# P03_SOM_CONNECTOR.net
KiCad netlist of a schematic drawn in Altium Designer
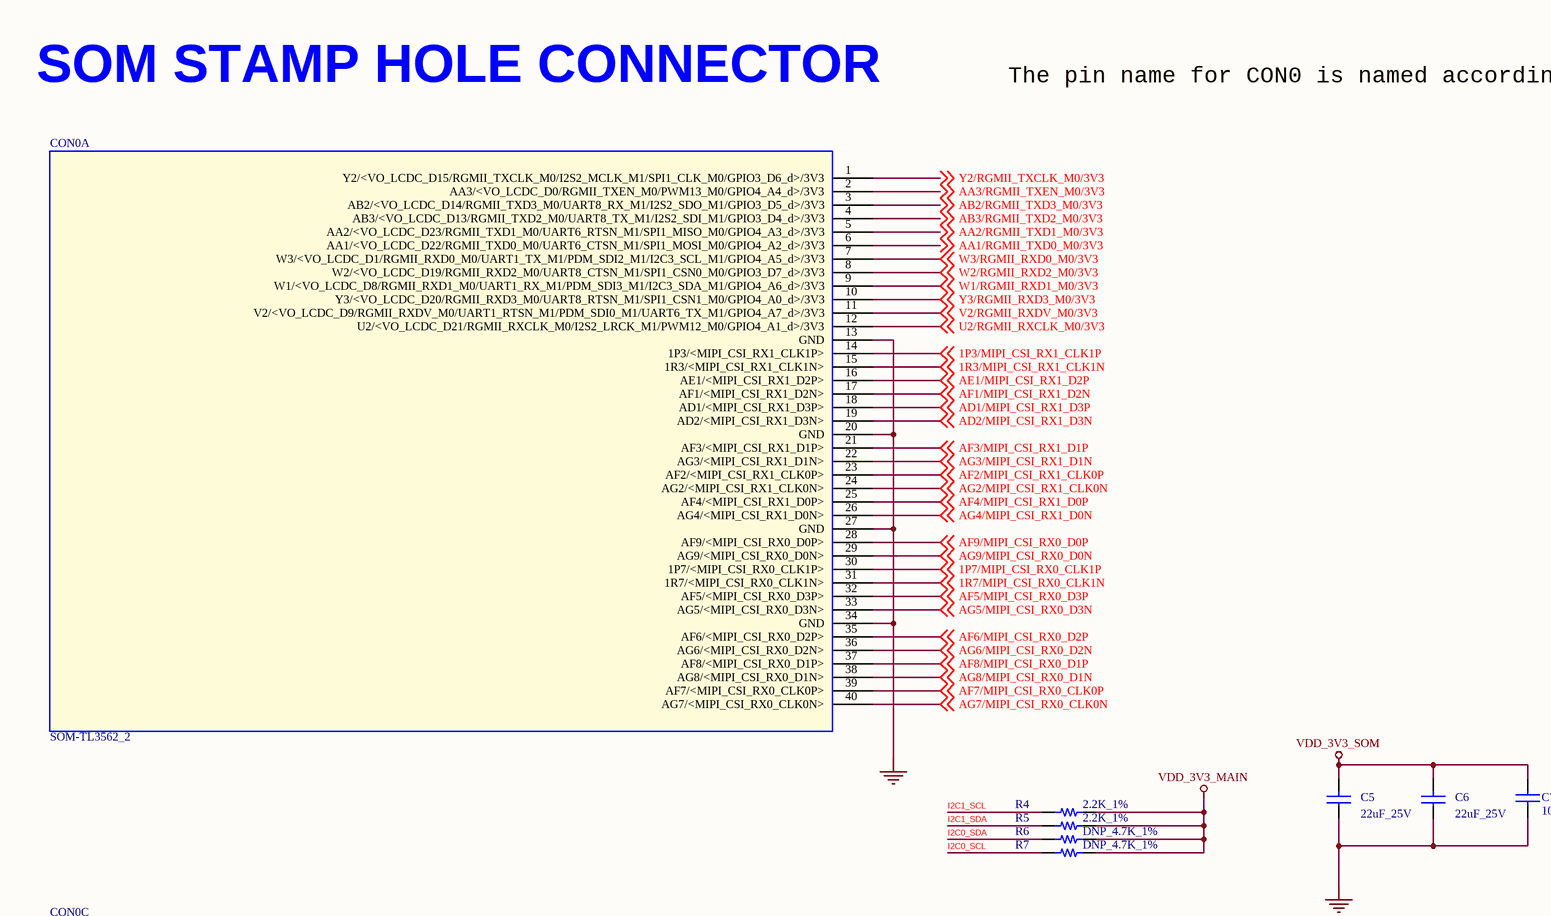
[diagram p0: P03_SOM CONNECTOR.SchDoc, top left]
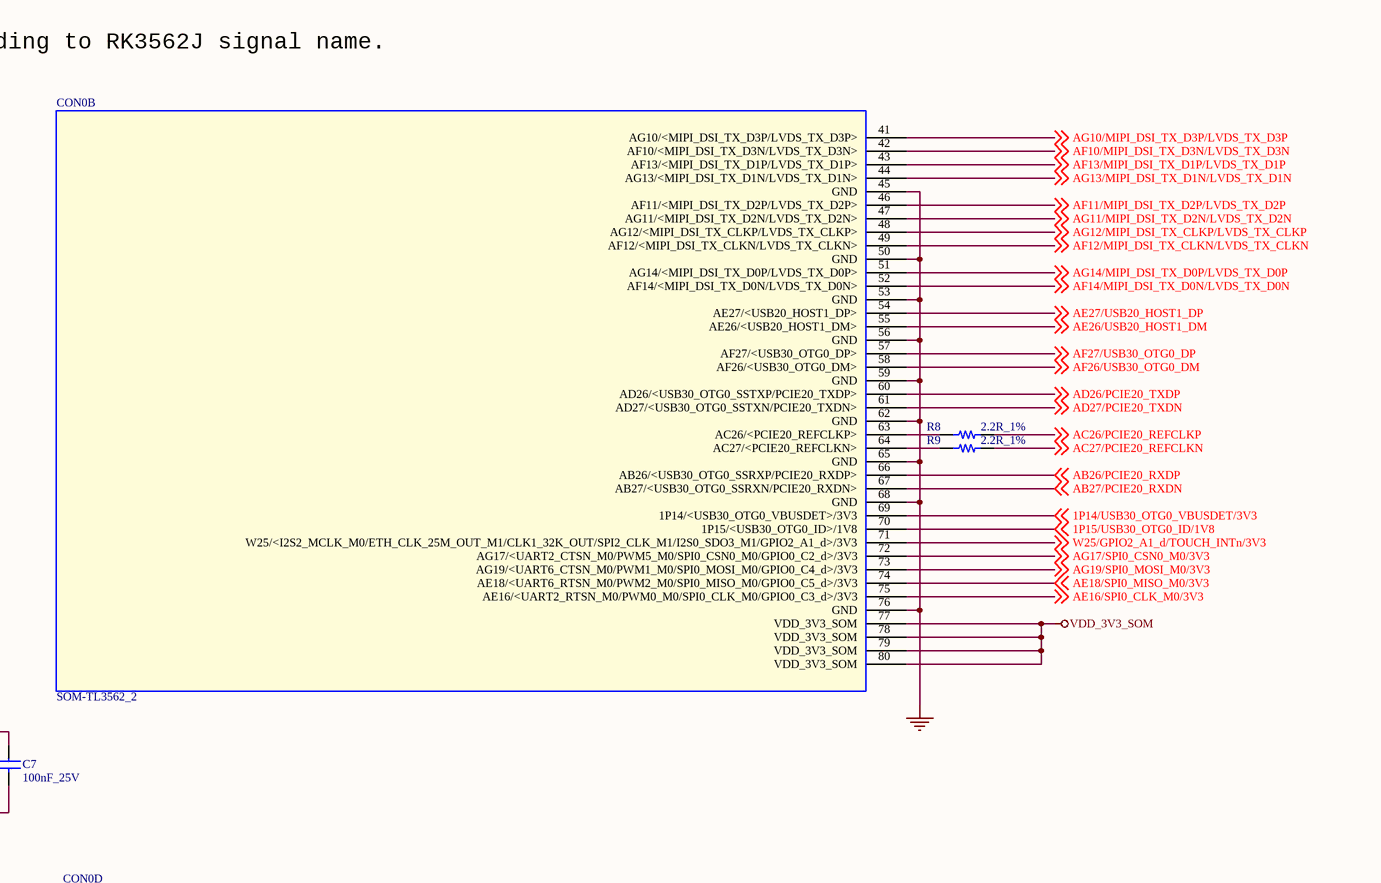
[diagram p1: P03_SOM CONNECTOR.SchDoc, top right]
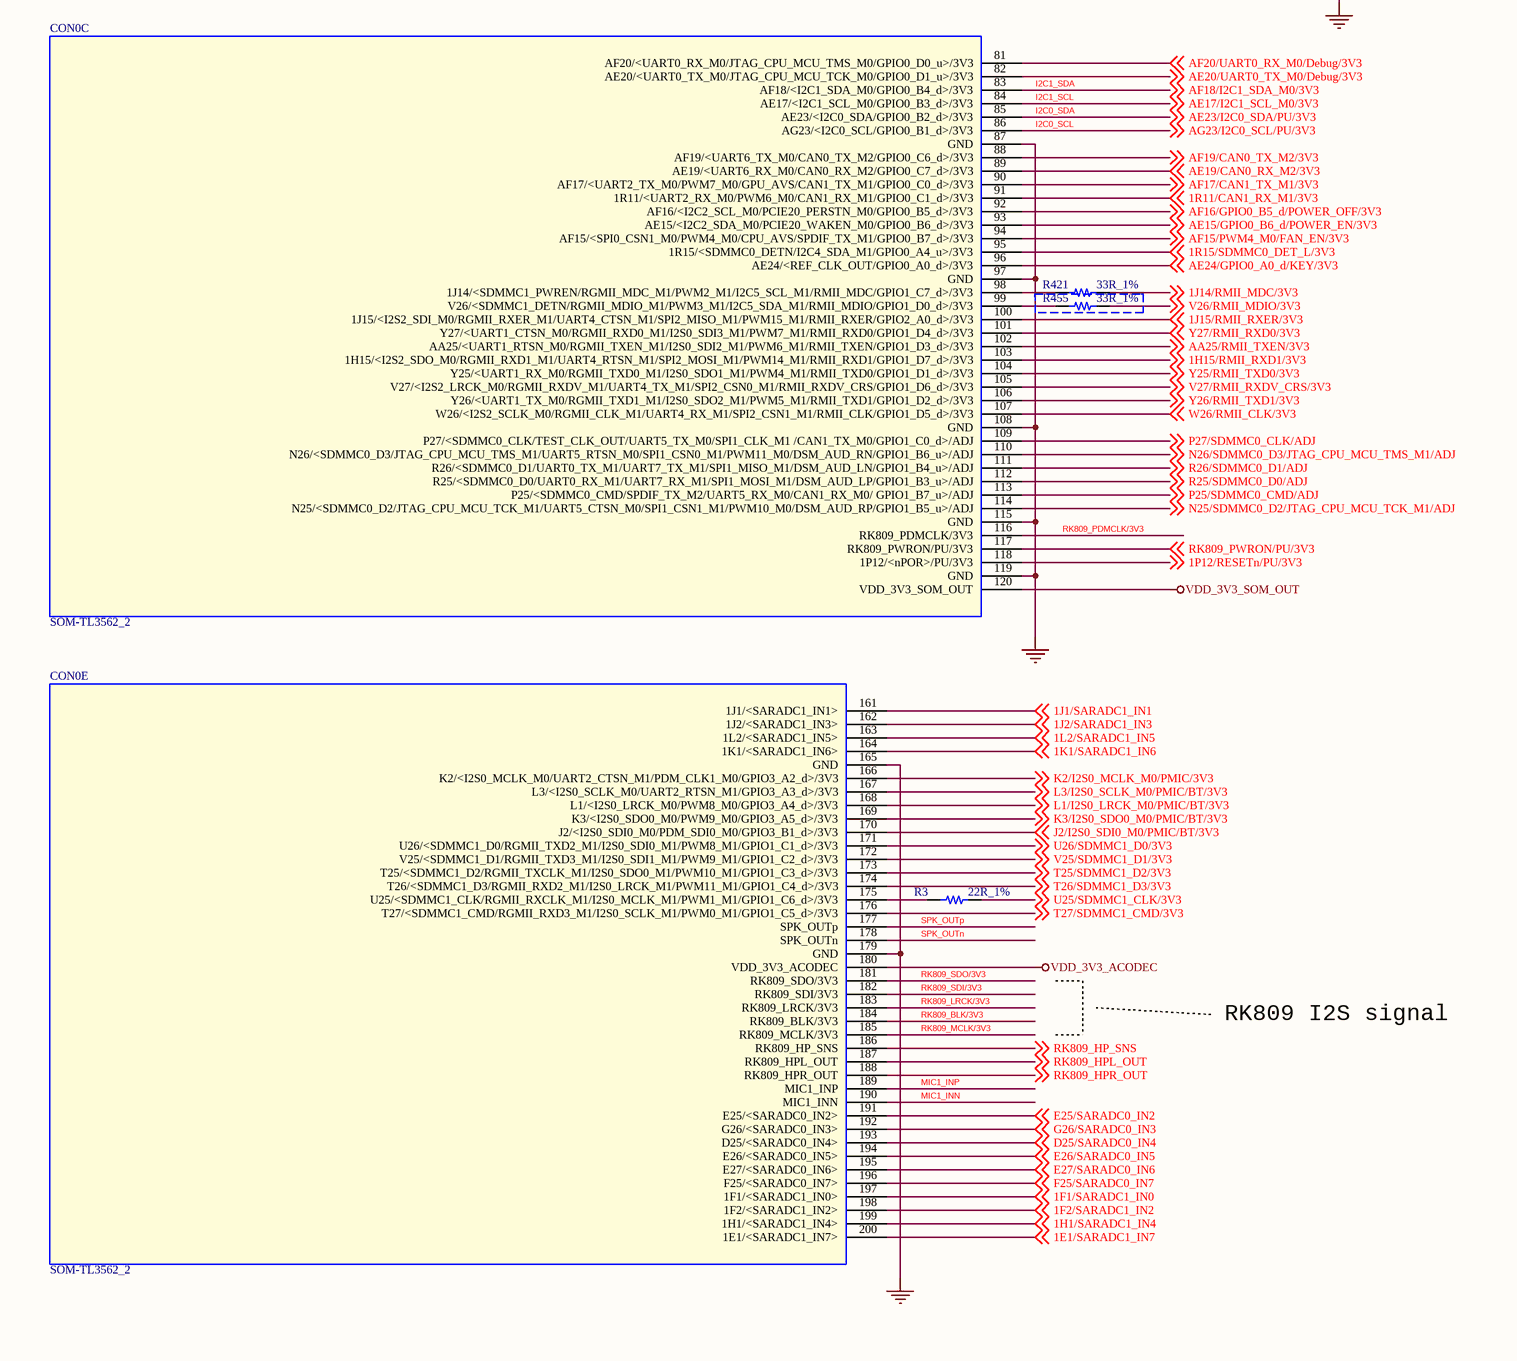
[diagram p2: P03_SOM CONNECTOR.SchDoc, bottom left]
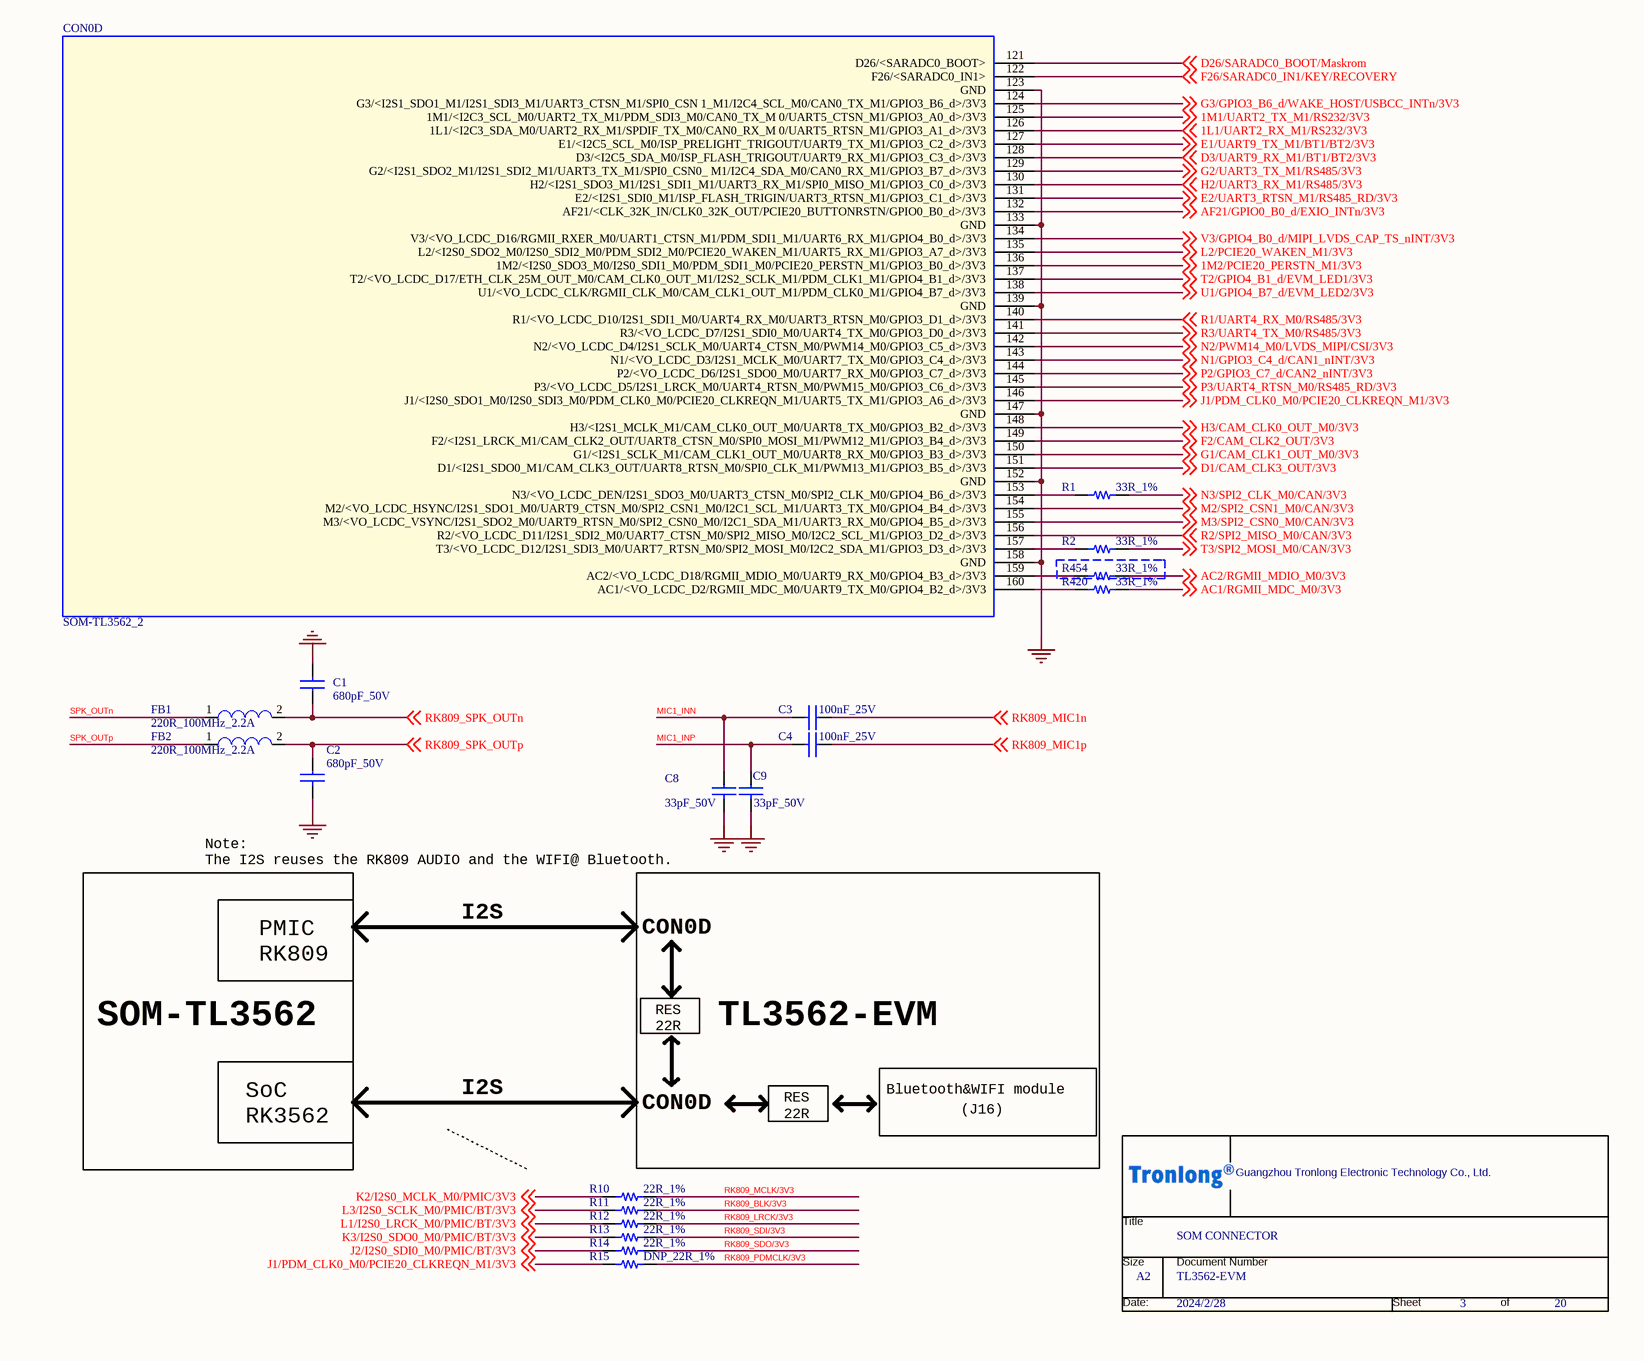
[diagram p3: P03_SOM CONNECTOR.SchDoc, bottom right]

(export (version "E")
  (design (tool "Eeschema 10.0.6"))
  (components
    (comp (ref "C1")
      (value "680pF_50V")
      (footprint "C0603")
      (description "贴片陶瓷电容,680pF,5%,50V,COG")
      (fields
        (field (name "TOLERANCE") "5%")
        (field (name "VOLTAGE") "50V")
        (field (name "CREATED BY") "JJJ")
      )
      (libsource (lib "*") (part "CAP NP_Dup3"))
    )
    (comp (ref "C2")
      (value "680pF_50V")
      (footprint "C0603")
      (description "贴片陶瓷电容,680pF,5%,50V,COG")
      (fields
        (field (name "VOLTAGE") "50V")
        (field (name "TOLERANCE") "5%")
        (field (name "CREATED BY") "JJJ")
      )
      (libsource (lib "*") (part "CAP NP_Dup3"))
    )
    (comp (ref "C3")
      (value "100nF_25V")
      (footprint "C0402")
      (description "贴片陶瓷电容,100nF,10%,25V,X5R")
      (fields
        (field (name "VOLTAGE") "10V")
        (field (name "TOLERANCE") "10%")
        (field (name "CREATED BY") "JJJ")
      )
      (libsource (lib "*") (part "CAP NP_Dup3"))
    )
    (comp (ref "C4")
      (value "100nF_25V")
      (footprint "C0402")
      (description "贴片陶瓷电容,100nF,10%,25V,X5R")
      (fields
        (field (name "TOLERANCE") "10%")
        (field (name "VOLTAGE") "10V")
        (field (name "CREATED BY") "JJJ")
      )
      (libsource (lib "*") (part "CAP NP_Dup3"))
    )
    (comp (ref "C5")
      (value "22uF_25V")
      (footprint "C0805")
      (description "贴片陶瓷电容,22uF,20%,25V,X5R")
      (fields
        (field (name "TOLERANCE") "10%")
        (field (name "VOLTAGE") "10V")
        (field (name "CREATED BY") "JJJ")
      )
      (libsource (lib "*") (part "CAP NP"))
    )
    (comp (ref "C6")
      (value "22uF_25V")
      (footprint "C0805")
      (description "贴片陶瓷电容,22uF,20%,25V,X5R")
      (fields
        (field (name "TOLERANCE") "10%")
        (field (name "VOLTAGE") "10V")
        (field (name "CREATED BY") "JJJ")
      )
      (libsource (lib "*") (part "CAP NP"))
    )
    (comp (ref "C7")
      (value "100nF_25V")
      (footprint "C0402")
      (description "贴片陶瓷电容,100nF,10%,25V,X5R")
      (fields
        (field (name "VOLTAGE") "10V")
        (field (name "TOLERANCE") "10%")
        (field (name "CREATED BY") "JJJ")
      )
      (libsource (lib "*") (part "CAP NP"))
    )
    (comp (ref "C8")
      (value "33pF_50V")
      (footprint "C0603")
      (description "贴片陶瓷电容,33pF,5%,50V,COG")
      (fields
        (field (name "VOLTAGE") "50V")
        (field (name "TOLERANCE") "5%")
        (field (name "CREATED BY") "JJJ")
      )
      (libsource (lib "*") (part "CAP NP_Dup3"))
    )
    (comp (ref "C9")
      (value "33pF_50V")
      (footprint "C0603")
      (description "贴片陶瓷电容,33pF,5%,50V,COG")
      (fields
        (field (name "VOLTAGE") "50V")
        (field (name "TOLERANCE") "5%")
        (field (name "CREATED BY") "JJJ")
      )
      (libsource (lib "*") (part "CAP NP_Dup3"))
    )
    (comp (ref "CON0")
      (value "SOM-TL3562_2")
      (footprint "TL3562-MiniEVM-new:SMD_200P_45x45_TL3562")
      (fields
        (field (name "MANUFACTURER") "广州创龙电子科技有限公司（Tronlong）")
        (field (name "MANUFACTURER PARTNUMBER") "SMD_200P_45x45_TL3562")
      )
      (libsource (lib "*") (part "SOM-TL3562_2"))
    )
    (comp (ref "FB1")
      (value "220R_100MHz_2.2A")
      (footprint "L0603")
      (description "磁珠,50mΩ,2.2A,220R@100MHz")
      (fields
        (field (name "MANUFACTURER PARTNUMBER") "UPZ1608U221-2R2TF")
        (field (name "MANUFACTURER") "深圳顺络电子股份有限公司（Sunlord）")
        (field (name "CREATED BY") "YTL")
      )
      (libsource (lib "*") (part "BEAD"))
    )
    (comp (ref "FB2")
      (value "220R_100MHz_2.2A")
      (footprint "L0603")
      (description "磁珠,50mΩ,2.2A,220R@100MHz")
      (fields
        (field (name "MANUFACTURER") "深圳顺络电子股份有限公司（Sunlord）")
        (field (name "MANUFACTURER PARTNUMBER") "UPZ1608U221-2R2TF")
        (field (name "CREATED BY") "YTL")
      )
      (libsource (lib "*") (part "BEAD"))
    )
    (comp (ref "R1")
      (value "33R_1%")
      (footprint "R0402")
      (description "贴片电阻,33R,±1%,1/16W")
      (libsource (lib "*") (part "Resistor_Dup3"))
    )
    (comp (ref "R2")
      (value "33R_1%")
      (footprint "R0402")
      (description "贴片电阻,33R,±1%,1/16W")
      (libsource (lib "*") (part "Resistor_Dup3"))
    )
    (comp (ref "R3")
      (value "22R_1%")
      (footprint "R0402")
      (description "贴片电阻,22R,±1%,1/16W")
      (libsource (lib "*") (part "Resistor_Dup3"))
    )
    (comp (ref "R4")
      (value "2.2K_1%")
      (footprint "R0603")
      (description "贴片电阻,2.2K,±1%,1/10W")
      (libsource (lib "*") (part "Resistor_Dup3"))
    )
    (comp (ref "R5")
      (value "2.2K_1%")
      (footprint "R0603")
      (description "贴片电阻,2.2K,±1%,1/10W")
      (libsource (lib "*") (part "Resistor_Dup3"))
    )
    (comp (ref "R6")
      (value "DNP_4.7K_1%")
      (footprint "R0402")
      (description "贴片电阻,4.7K,±1%,1/16W")
      (libsource (lib "*") (part "Resistor_Dup3"))
    )
    (comp (ref "R7")
      (value "DNP_4.7K_1%")
      (footprint "R0402")
      (description "贴片电阻,4.7K,±1%,1/16W")
      (libsource (lib "*") (part "Resistor_Dup3"))
    )
    (comp (ref "R8")
      (value "2.2R_1%")
      (footprint "R0402")
      (description "贴片电阻,2.2R,±1%,1/16W")
      (libsource (lib "*") (part "Resistor_Dup3"))
    )
    (comp (ref "R9")
      (value "2.2R_1%")
      (footprint "R0402")
      (description "贴片电阻,2.2R,±1%,1/16W")
      (libsource (lib "*") (part "Resistor_Dup3"))
    )
    (comp (ref "R10")
      (value "22R_1%")
      (footprint "R0402")
      (description "贴片电阻,22R,±1%,1/16W")
      (libsource (lib "*") (part "Resistor_Dup3"))
    )
    (comp (ref "R11")
      (value "22R_1%")
      (footprint "R0402")
      (description "贴片电阻,22R,±1%,1/16W")
      (libsource (lib "*") (part "Resistor_Dup3"))
    )
    (comp (ref "R12")
      (value "22R_1%")
      (footprint "R0402")
      (description "贴片电阻,22R,±1%,1/16W")
      (libsource (lib "*") (part "Resistor_Dup3"))
    )
    (comp (ref "R13")
      (value "22R_1%")
      (footprint "R0402")
      (description "贴片电阻,22R,±1%,1/16W")
      (libsource (lib "*") (part "Resistor_Dup3"))
    )
    (comp (ref "R14")
      (value "22R_1%")
      (footprint "R0402")
      (description "贴片电阻,22R,±1%,1/16W")
      (libsource (lib "*") (part "Resistor_Dup3"))
    )
    (comp (ref "R15")
      (value "DNP_22R_1%")
      (footprint "R0402")
      (description "贴片电阻,22R,±1%,1/16W")
      (libsource (lib "*") (part "Resistor_Dup3"))
    )
    (comp (ref "R420")
      (value "33R_1%")
      (footprint "R0402")
      (description "贴片电阻,33R,±1%,1/16W")
      (libsource (lib "*") (part "Resistor_Dup3"))
    )
    (comp (ref "R421")
      (value "33R_1%")
      (footprint "R0402")
      (description "贴片电阻,33R,±1%,1/16W")
      (libsource (lib "*") (part "Resistor_Dup3"))
    )
    (comp (ref "R454")
      (value "33R_1%")
      (footprint "R0402")
      (description "贴片电阻,33R,±1%,1/16W")
      (libsource (lib "*") (part "Resistor_Dup3"))
    )
    (comp (ref "R455")
      (value "33R_1%")
      (footprint "R0402")
      (description "贴片电阻,33R,±1%,1/16W")
      (libsource (lib "*") (part "Resistor_Dup3"))
    )
  )
  (nets
    (net (code "1") (name "/MIC1_INN") (class "Default")
      (node (ref "C3") (pin "2") (pinfunction "2_2") (pintype "passive"))
      (node (ref "C8") (pin "1") (pinfunction "1_1") (pintype "passive"))
      (node (ref "CON0") (pin "190") (pinfunction "MIC1_INN_190") (pintype "passive"))
    )
    (net (code "2") (name "/MIC1_INP") (class "Default")
      (node (ref "C4") (pin "2") (pinfunction "2_2") (pintype "passive"))
      (node (ref "C9") (pin "1") (pinfunction "1_1") (pintype "passive"))
      (node (ref "CON0") (pin "189") (pinfunction "MIC1_INP_189") (pintype "passive"))
    )
    (net (code "3") (name "/RK809_BLK{slash}3V3") (class "Default")
      (node (ref "CON0") (pin "184") (pinfunction "RK809_BLK/3V3_184") (pintype "passive"))
      (node (ref "R11") (pin "2") (pinfunction "2_2") (pintype "passive"))
    )
    (net (code "4") (name "/RK809_LRCK{slash}3V3") (class "Default")
      (node (ref "CON0") (pin "183") (pinfunction "RK809_LRCK/3V3_183") (pintype "passive"))
      (node (ref "R12") (pin "2") (pinfunction "2_2") (pintype "passive"))
    )
    (net (code "5") (name "/RK809_MCLK{slash}3V3") (class "Default")
      (node (ref "CON0") (pin "185") (pinfunction "RK809_MCLK/3V3_185") (pintype "passive"))
      (node (ref "R10") (pin "2") (pinfunction "2_2") (pintype "passive"))
    )
    (net (code "6") (name "/RK809_PDMCLK{slash}3V3") (class "Default")
      (node (ref "CON0") (pin "116") (pinfunction "RK809_PDMCLK/3V3_116") (pintype "passive"))
      (node (ref "R15") (pin "2") (pinfunction "2_2") (pintype "passive"))
    )
    (net (code "7") (name "/RK809_SDI{slash}3V3") (class "Default")
      (node (ref "CON0") (pin "182") (pinfunction "RK809_SDI/3V3_182") (pintype "passive"))
      (node (ref "R13") (pin "2") (pinfunction "2_2") (pintype "passive"))
    )
    (net (code "8") (name "/RK809_SDO{slash}3V3") (class "Default")
      (node (ref "CON0") (pin "181") (pinfunction "RK809_SDO/3V3_181") (pintype "passive"))
      (node (ref "R14") (pin "2") (pinfunction "2_2") (pintype "passive"))
    )
    (net (code "9") (name "/SPK_OUTn") (class "Default")
      (node (ref "CON0") (pin "178") (pinfunction "SPK_OUTn_178") (pintype "passive"))
      (node (ref "FB1") (pin "1") (pinfunction "1_1") (pintype "passive"))
    )
    (net (code "10") (name "/SPK_OUTp") (class "Default")
      (node (ref "CON0") (pin "177") (pinfunction "SPK_OUTp_177") (pintype "passive"))
      (node (ref "FB2") (pin "1") (pinfunction "1_1") (pintype "passive"))
    )
    (net (code "11") (name "1E1{slash}SARADC1_IN7") (class "Default")
      (node (ref "CON0") (pin "200") (pinfunction "1E1/<SARADC1_IN7>_200") (pintype "passive"))
    )
    (net (code "12") (name "1F1{slash}SARADC1_IN0") (class "Default")
      (node (ref "CON0") (pin "197") (pinfunction "1F1/<SARADC1_IN0>_197") (pintype "passive"))
    )
    (net (code "13") (name "1F2{slash}SARADC1_IN2") (class "Default")
      (node (ref "CON0") (pin "198") (pinfunction "1F2/<SARADC1_IN2>_198") (pintype "passive"))
    )
    (net (code "14") (name "1H1{slash}SARADC1_IN4") (class "Default")
      (node (ref "CON0") (pin "199") (pinfunction "1H1/<SARADC1_IN4>_199") (pintype "passive"))
    )
    (net (code "15") (name "1H15{slash}RMII_RXD1{slash}3V3") (class "Default")
      (node (ref "CON0") (pin "103") (pinfunction "1H15/<I2S2_SDO_M0/RGMII_RXD1_M1/UART4_RTSN_M1/SPI2_MOSI_M1/PWM14_M1/RMII_RXD1/GPIO1_D7_d>/3V3_103") (pintype "passive"))
    )
    (net (code "16") (name "1J1{slash}SARADC1_IN1") (class "Default")
      (node (ref "CON0") (pin "161") (pinfunction "1J1/<SARADC1_IN1>_161") (pintype "passive"))
    )
    (net (code "17") (name "1J2{slash}SARADC1_IN3") (class "Default")
      (node (ref "CON0") (pin "162") (pinfunction "1J2/<SARADC1_IN3>_162") (pintype "passive"))
    )
    (net (code "18") (name "1J14{slash}RMII_MDC{slash}3V3") (class "Default")
      (node (ref "R421") (pin "2") (pinfunction "2_2") (pintype "passive"))
    )
    (net (code "19") (name "1J15{slash}RMII_RXER{slash}3V3") (class "Default")
      (node (ref "CON0") (pin "100") (pinfunction "1J15/<I2S2_SDI_M0/RGMII_RXER_M1/UART4_CTSN_M1/SPI2_MISO_M1/PWM15_M1/RMII_RXER/GPIO2_A0_d>/3V3_100") (pintype "passive"))
    )
    (net (code "20") (name "1K1{slash}SARADC1_IN6") (class "Default")
      (node (ref "CON0") (pin "164") (pinfunction "1K1/<SARADC1_IN6>_164") (pintype "passive"))
    )
    (net (code "21") (name "1L1{slash}UART2_RX_M1{slash}RS232{slash}3V3") (class "Default")
      (node (ref "CON0") (pin "126") (pinfunction "1L1/<I2C3_SDA_M0/UART2_RX_M1/SPDIF_TX_M0/CAN0_RX_M\n0/UART5_RTSN_M1/GPIO3_A1_d>/3V3_126") (pintype "passive"))
    )
    (net (code "22") (name "1L2{slash}SARADC1_IN5") (class "Default")
      (node (ref "CON0") (pin "163") (pinfunction "1L2/<SARADC1_IN5>_163") (pintype "passive"))
    )
    (net (code "23") (name "1M1{slash}UART2_TX_M1{slash}RS232{slash}3V3") (class "Default")
      (node (ref "CON0") (pin "125") (pinfunction "1M1/<I2C3_SCL_M0/UART2_TX_M1/PDM_SDI3_M0/CAN0_TX_M\n0/UART5_CTSN_M1/GPIO3_A0_d>/3V3_125") (pintype "passive"))
    )
    (net (code "24") (name "1M2{slash}PCIE20_PERSTN_M1{slash}3V3") (class "Default")
      (node (ref "CON0") (pin "136") (pinfunction "1M2/<I2S0_SDO3_M0/I2S0_SDI1_M0/PDM_SDI1_M0/PCIE20_PERSTN_M1/GPIO3_B0_d>/3V3_136") (pintype "passive"))
    )
    (net (code "25") (name "1P3{slash}MIPI_CSI_RX1_CLK1P") (class "Default")
      (node (ref "CON0") (pin "14") (pinfunction "1P3/<MIPI_CSI_RX1_CLK1P>_14") (pintype "passive"))
    )
    (net (code "26") (name "1P7{slash}MIPI_CSI_RX0_CLK1P") (class "Default")
      (node (ref "CON0") (pin "30") (pinfunction "1P7/<MIPI_CSI_RX0_CLK1P>_30") (pintype "passive"))
    )
    (net (code "27") (name "1P12{slash}RESETn{slash}PU{slash}3V3") (class "Default")
      (node (ref "CON0") (pin "118") (pinfunction "1P12/<nPOR>/PU/3V3_118") (pintype "passive"))
    )
    (net (code "28") (name "1P14{slash}USB30_OTG0_VBUSDET{slash}3V3") (class "Default")
      (node (ref "CON0") (pin "69") (pinfunction "1P14/<USB30_OTG0_VBUSDET>/3V3_69") (pintype "passive"))
    )
    (net (code "29") (name "1P15{slash}USB30_OTG0_ID{slash}1V8") (class "Default")
      (node (ref "CON0") (pin "70") (pinfunction "1P15/<USB30_OTG0_ID>/1V8_70") (pintype "passive"))
    )
    (net (code "30") (name "1R3{slash}MIPI_CSI_RX1_CLK1N") (class "Default")
      (node (ref "CON0") (pin "15") (pinfunction "1R3/<MIPI_CSI_RX1_CLK1N>_15") (pintype "passive"))
    )
    (net (code "31") (name "1R7{slash}MIPI_CSI_RX0_CLK1N") (class "Default")
      (node (ref "CON0") (pin "31") (pinfunction "1R7/<MIPI_CSI_RX0_CLK1N>_31") (pintype "passive"))
    )
    (net (code "32") (name "1R11{slash}CAN1_RX_M1{slash}3V3") (class "Default")
      (node (ref "CON0") (pin "91") (pinfunction "1R11/<UART2_RX_M0/PWM6_M0/CAN1_RX_M1/GPIO0_C1_d>/3V3_91") (pintype "passive"))
    )
    (net (code "33") (name "1R15{slash}SDMMC0_DET_L{slash}3V3") (class "Default")
      (node (ref "CON0") (pin "95") (pinfunction "1R15/<SDMMC0_DETN/I2C4_SDA_M1/GPIO0_A4_u>/3V3_95") (pintype "passive"))
    )
    (net (code "34") (name "AA1{slash}RGMII_TXD0_M0{slash}3V3") (class "Default")
      (node (ref "CON0") (pin "6") (pinfunction "AA1/<VO_LCDC_D22/RGMII_TXD0_M0/UART6_CTSN_M1/SPI1_MOSI_M0/GPIO4_A2_d>/3V3_6") (pintype "passive"))
    )
    (net (code "35") (name "AA2{slash}RGMII_TXD1_M0{slash}3V3") (class "Default")
      (node (ref "CON0") (pin "5") (pinfunction "AA2/<VO_LCDC_D23/RGMII_TXD1_M0/UART6_RTSN_M1/SPI1_MISO_M0/GPIO4_A3_d>/3V3_5") (pintype "passive"))
    )
    (net (code "36") (name "AA3{slash}RGMII_TXEN_M0{slash}3V3") (class "Default")
      (node (ref "CON0") (pin "2") (pinfunction "AA3/<VO_LCDC_D0/RGMII_TXEN_M0/PWM13_M0/GPIO4_A4_d>/3V3_2") (pintype "passive"))
    )
    (net (code "37") (name "AA25{slash}RMII_TXEN{slash}3V3") (class "Default")
      (node (ref "CON0") (pin "102") (pinfunction "AA25/<UART1_RTSN_M0/RGMII_TXEN_M1/I2S0_SDI2_M1/PWM6_M1/RMII_TXEN/GPIO1_D3_d>/3V3_102") (pintype "passive"))
    )
    (net (code "38") (name "AB2{slash}RGMII_TXD3_M0{slash}3V3") (class "Default")
      (node (ref "CON0") (pin "3") (pinfunction "AB2/<VO_LCDC_D14/RGMII_TXD3_M0/UART8_RX_M1/I2S2_SDO_M1/GPIO3_D5_d>/3V3_3") (pintype "passive"))
    )
    (net (code "39") (name "AB3{slash}RGMII_TXD2_M0{slash}3V3") (class "Default")
      (node (ref "CON0") (pin "4") (pinfunction "AB3/<VO_LCDC_D13/RGMII_TXD2_M0/UART8_TX_M1/I2S2_SDI_M1/GPIO3_D4_d>/3V3_4") (pintype "passive"))
    )
    (net (code "40") (name "AB26{slash}PCIE20_RXDP") (class "Default")
      (node (ref "CON0") (pin "66") (pinfunction "AB26/<USB30_OTG0_SSRXP/PCIE20_RXDP>_66") (pintype "passive"))
    )
    (net (code "41") (name "AB27{slash}PCIE20_RXDN") (class "Default")
      (node (ref "CON0") (pin "67") (pinfunction "AB27/<USB30_OTG0_SSRXN/PCIE20_RXDN>_67") (pintype "passive"))
    )
    (net (code "42") (name "AC1{slash}RGMII_MDC_M0{slash}3V3") (class "Default")
      (node (ref "R420") (pin "2") (pinfunction "2_2") (pintype "passive"))
    )
    (net (code "43") (name "AC2{slash}RGMII_MDIO_M0{slash}3V3") (class "Default")
      (node (ref "R454") (pin "2") (pinfunction "2_2") (pintype "passive"))
    )
    (net (code "44") (name "AC26{slash}PCIE20_REFCLKP") (class "Default")
      (node (ref "R8") (pin "2") (pinfunction "2_2") (pintype "passive"))
    )
    (net (code "45") (name "AC27{slash}PCIE20_REFCLKN") (class "Default")
      (node (ref "R9") (pin "2") (pinfunction "2_2") (pintype "passive"))
    )
    (net (code "46") (name "AD1{slash}MIPI_CSI_RX1_D3P") (class "Default")
      (node (ref "CON0") (pin "18") (pinfunction "AD1/<MIPI_CSI_RX1_D3P>_18") (pintype "passive"))
    )
    (net (code "47") (name "AD2{slash}MIPI_CSI_RX1_D3N") (class "Default")
      (node (ref "CON0") (pin "19") (pinfunction "AD2/<MIPI_CSI_RX1_D3N>_19") (pintype "passive"))
    )
    (net (code "48") (name "AD26{slash}PCIE20_TXDP") (class "Default")
      (node (ref "CON0") (pin "60") (pinfunction "AD26/<USB30_OTG0_SSTXP/PCIE20_TXDP>_60") (pintype "passive"))
    )
    (net (code "49") (name "AD27{slash}PCIE20_TXDN") (class "Default")
      (node (ref "CON0") (pin "61") (pinfunction "AD27/<USB30_OTG0_SSTXN/PCIE20_TXDN>_61") (pintype "passive"))
    )
    (net (code "50") (name "AE1{slash}MIPI_CSI_RX1_D2P") (class "Default")
      (node (ref "CON0") (pin "16") (pinfunction "AE1/<MIPI_CSI_RX1_D2P>_16") (pintype "passive"))
    )
    (net (code "51") (name "AE15{slash}GPIO0_B6_d{slash}POWER_EN{slash}3V3") (class "Default")
      (node (ref "CON0") (pin "93") (pinfunction "AE15/<I2C2_SDA_M0/PCIE20_WAKEN_M0/GPIO0_B6_d>/3V3_93") (pintype "passive"))
    )
    (net (code "52") (name "AE16{slash}SPI0_CLK_M0{slash}3V3") (class "Default")
      (node (ref "CON0") (pin "75") (pinfunction "AE16/<UART2_RTSN_M0/PWM0_M0/SPI0_CLK_M0/GPIO0_C3_d>/3V3_75") (pintype "passive"))
    )
    (net (code "53") (name "AE17{slash}I2C1_SCL_M0{slash}3V3") (class "Default")
      (node (ref "CON0") (pin "84") (pinfunction "AE17/<I2C1_SCL_M0/GPIO0_B3_d>/3V3_84") (pintype "passive"))
      (node (ref "R4") (pin "1") (pinfunction "1_1") (pintype "passive"))
    )
    (net (code "54") (name "AE18{slash}SPI0_MISO_M0{slash}3V3") (class "Default")
      (node (ref "CON0") (pin "74") (pinfunction "AE18/<UART6_RTSN_M0/PWM2_M0/SPI0_MISO_M0/GPIO0_C5_d>/3V3_74") (pintype "passive"))
    )
    (net (code "55") (name "AE19{slash}CAN0_RX_M2{slash}3V3") (class "Default")
      (node (ref "CON0") (pin "89") (pinfunction "AE19/<UART6_RX_M0/CAN0_RX_M2/GPIO0_C7_d>/3V3_89") (pintype "passive"))
    )
    (net (code "56") (name "AE20{slash}UART0_TX_M0{slash}Debug{slash}3V3") (class "Default")
      (node (ref "CON0") (pin "82") (pinfunction "AE20/<UART0_TX_M0/JTAG_CPU_MCU_TCK_M0/GPIO0_D1_u>/3V3_82") (pintype "passive"))
    )
    (net (code "57") (name "AE23{slash}I2C0_SDA{slash}PU{slash}3V3") (class "Default")
      (node (ref "CON0") (pin "85") (pinfunction "AE23/<I2C0_SDA/GPIO0_B2_d>/3V3_85") (pintype "passive"))
      (node (ref "R6") (pin "1") (pinfunction "1_1") (pintype "passive"))
    )
    (net (code "58") (name "AE24{slash}GPIO0_A0_d{slash}KEY{slash}3V3") (class "Default")
      (node (ref "CON0") (pin "96") (pinfunction "AE24/<REF_CLK_OUT/GPIO0_A0_d>/3V3_96") (pintype "passive"))
    )
    (net (code "59") (name "AE26{slash}USB20_HOST1_DM") (class "Default")
      (node (ref "CON0") (pin "55") (pinfunction "AE26/<USB20_HOST1_DM>_55") (pintype "passive"))
    )
    (net (code "60") (name "AE27{slash}USB20_HOST1_DP") (class "Default")
      (node (ref "CON0") (pin "54") (pinfunction "AE27/<USB20_HOST1_DP>_54") (pintype "passive"))
    )
    (net (code "61") (name "AF1{slash}MIPI_CSI_RX1_D2N") (class "Default")
      (node (ref "CON0") (pin "17") (pinfunction "AF1/<MIPI_CSI_RX1_D2N>_17") (pintype "passive"))
    )
    (net (code "62") (name "AF2{slash}MIPI_CSI_RX1_CLK0P") (class "Default")
      (node (ref "CON0") (pin "23") (pinfunction "AF2/<MIPI_CSI_RX1_CLK0P>_23") (pintype "passive"))
    )
    (net (code "63") (name "AF3{slash}MIPI_CSI_RX1_D1P") (class "Default")
      (node (ref "CON0") (pin "21") (pinfunction "AF3/<MIPI_CSI_RX1_D1P>_21") (pintype "passive"))
    )
    (net (code "64") (name "AF4{slash}MIPI_CSI_RX1_D0P") (class "Default")
      (node (ref "CON0") (pin "25") (pinfunction "AF4/<MIPI_CSI_RX1_D0P>_25") (pintype "passive"))
    )
    (net (code "65") (name "AF5{slash}MIPI_CSI_RX0_D3P") (class "Default")
      (node (ref "CON0") (pin "32") (pinfunction "AF5/<MIPI_CSI_RX0_D3P>_32") (pintype "passive"))
    )
    (net (code "66") (name "AF6{slash}MIPI_CSI_RX0_D2P") (class "Default")
      (node (ref "CON0") (pin "35") (pinfunction "AF6/<MIPI_CSI_RX0_D2P>_35") (pintype "passive"))
    )
    (net (code "67") (name "AF7{slash}MIPI_CSI_RX0_CLK0P") (class "Default")
      (node (ref "CON0") (pin "39") (pinfunction "AF7/<MIPI_CSI_RX0_CLK0P>_39") (pintype "passive"))
    )
    (net (code "68") (name "AF8{slash}MIPI_CSI_RX0_D1P") (class "Default")
      (node (ref "CON0") (pin "37") (pinfunction "AF8/<MIPI_CSI_RX0_D1P>_37") (pintype "passive"))
    )
    (net (code "69") (name "AF9{slash}MIPI_CSI_RX0_D0P") (class "Default")
      (node (ref "CON0") (pin "28") (pinfunction "AF9/<MIPI_CSI_RX0_D0P>_28") (pintype "passive"))
    )
    (net (code "70") (name "AF10{slash}MIPI_DSI_TX_D3N{slash}LVDS_TX_D3N") (class "Default")
      (node (ref "CON0") (pin "42") (pinfunction "AF10/<MIPI_DSI_TX_D3N/LVDS_TX_D3N>_42") (pintype "passive"))
    )
    (net (code "71") (name "AF11{slash}MIPI_DSI_TX_D2P{slash}LVDS_TX_D2P") (class "Default")
      (node (ref "CON0") (pin "46") (pinfunction "AF11/<MIPI_DSI_TX_D2P/LVDS_TX_D2P>_46") (pintype "passive"))
    )
    (net (code "72") (name "AF12{slash}MIPI_DSI_TX_CLKN{slash}LVDS_TX_CLKN") (class "Default")
      (node (ref "CON0") (pin "49") (pinfunction "AF12/<MIPI_DSI_TX_CLKN/LVDS_TX_CLKN>_49") (pintype "passive"))
    )
    (net (code "73") (name "AF13{slash}MIPI_DSI_TX_D1P{slash}LVDS_TX_D1P") (class "Default")
      (node (ref "CON0") (pin "43") (pinfunction "AF13/<MIPI_DSI_TX_D1P/LVDS_TX_D1P>_43") (pintype "passive"))
    )
    (net (code "74") (name "AF14{slash}MIPI_DSI_TX_D0N{slash}LVDS_TX_D0N") (class "Default")
      (node (ref "CON0") (pin "52") (pinfunction "AF14/<MIPI_DSI_TX_D0N/LVDS_TX_D0N>_52") (pintype "passive"))
    )
    (net (code "75") (name "AF15{slash}PWM4_M0{slash}FAN_EN{slash}3V3") (class "Default")
      (node (ref "CON0") (pin "94") (pinfunction "AF15/<SPI0_CSN1_M0/PWM4_M0/CPU_AVS/SPDIF_TX_M1/GPIO0_B7_d>/3V3_94") (pintype "passive"))
    )
    (net (code "76") (name "AF16{slash}GPIO0_B5_d{slash}POWER_OFF{slash}3V3") (class "Default")
      (node (ref "CON0") (pin "92") (pinfunction "AF16/<I2C2_SCL_M0/PCIE20_PERSTN_M0/GPIO0_B5_d>/3V3_92") (pintype "passive"))
    )
    (net (code "77") (name "AF17{slash}CAN1_TX_M1{slash}3V3") (class "Default")
      (node (ref "CON0") (pin "90") (pinfunction "AF17/<UART2_TX_M0/PWM7_M0/GPU_AVS/CAN1_TX_M1/GPIO0_C0_d>/3V3_90") (pintype "passive"))
    )
    (net (code "78") (name "AF18{slash}I2C1_SDA_M0{slash}3V3") (class "Default")
      (node (ref "CON0") (pin "83") (pinfunction "AF18/<I2C1_SDA_M0/GPIO0_B4_d>/3V3_83") (pintype "passive"))
      (node (ref "R5") (pin "1") (pinfunction "1_1") (pintype "passive"))
    )
    (net (code "79") (name "AF19{slash}CAN0_TX_M2{slash}3V3") (class "Default")
      (node (ref "CON0") (pin "88") (pinfunction "AF19/<UART6_TX_M0/CAN0_TX_M2/GPIO0_C6_d>/3V3_88") (pintype "passive"))
    )
    (net (code "80") (name "AF20{slash}UART0_RX_M0{slash}Debug{slash}3V3") (class "Default")
      (node (ref "CON0") (pin "81") (pinfunction "AF20/<UART0_RX_M0/JTAG_CPU_MCU_TMS_M0/GPIO0_D0_u>/3V3_81") (pintype "passive"))
    )
    (net (code "81") (name "AF21{slash}GPIO0_B0_d{slash}EXIO_INTn{slash}3V3") (class "Default")
      (node (ref "CON0") (pin "132") (pinfunction "AF21/<CLK_32K_IN/CLK0_32K_OUT/PCIE20_BUTTONRSTN/GPIO0_B0_d>/3V3_132") (pintype "passive"))
    )
    (net (code "82") (name "AF26{slash}USB30_OTG0_DM") (class "Default")
      (node (ref "CON0") (pin "58") (pinfunction "AF26/<USB30_OTG0_DM>_58") (pintype "passive"))
    )
    (net (code "83") (name "AF27{slash}USB30_OTG0_DP") (class "Default")
      (node (ref "CON0") (pin "57") (pinfunction "AF27/<USB30_OTG0_DP>_57") (pintype "passive"))
    )
    (net (code "84") (name "AG2{slash}MIPI_CSI_RX1_CLK0N") (class "Default")
      (node (ref "CON0") (pin "24") (pinfunction "AG2/<MIPI_CSI_RX1_CLK0N>_24") (pintype "passive"))
    )
    (net (code "85") (name "AG3{slash}MIPI_CSI_RX1_D1N") (class "Default")
      (node (ref "CON0") (pin "22") (pinfunction "AG3/<MIPI_CSI_RX1_D1N>_22") (pintype "passive"))
    )
    (net (code "86") (name "AG4{slash}MIPI_CSI_RX1_D0N") (class "Default")
      (node (ref "CON0") (pin "26") (pinfunction "AG4/<MIPI_CSI_RX1_D0N>_26") (pintype "passive"))
    )
    (net (code "87") (name "AG5{slash}MIPI_CSI_RX0_D3N") (class "Default")
      (node (ref "CON0") (pin "33") (pinfunction "AG5/<MIPI_CSI_RX0_D3N>_33") (pintype "passive"))
    )
    (net (code "88") (name "AG6{slash}MIPI_CSI_RX0_D2N") (class "Default")
      (node (ref "CON0") (pin "36") (pinfunction "AG6/<MIPI_CSI_RX0_D2N>_36") (pintype "passive"))
    )
    (net (code "89") (name "AG7{slash}MIPI_CSI_RX0_CLK0N") (class "Default")
      (node (ref "CON0") (pin "40") (pinfunction "AG7/<MIPI_CSI_RX0_CLK0N>_40") (pintype "passive"))
    )
    (net (code "90") (name "AG8{slash}MIPI_CSI_RX0_D1N") (class "Default")
      (node (ref "CON0") (pin "38") (pinfunction "AG8/<MIPI_CSI_RX0_D1N>_38") (pintype "passive"))
    )
    (net (code "91") (name "AG9{slash}MIPI_CSI_RX0_D0N") (class "Default")
      (node (ref "CON0") (pin "29") (pinfunction "AG9/<MIPI_CSI_RX0_D0N>_29") (pintype "passive"))
    )
    (net (code "92") (name "AG10{slash}MIPI_DSI_TX_D3P{slash}LVDS_TX_D3P") (class "Default")
      (node (ref "CON0") (pin "41") (pinfunction "AG10/<MIPI_DSI_TX_D3P/LVDS_TX_D3P>_41") (pintype "passive"))
    )
    (net (code "93") (name "AG11{slash}MIPI_DSI_TX_D2N{slash}LVDS_TX_D2N") (class "Default")
      (node (ref "CON0") (pin "47") (pinfunction "AG11/<MIPI_DSI_TX_D2N/LVDS_TX_D2N>_47") (pintype "passive"))
    )
    (net (code "94") (name "AG12{slash}MIPI_DSI_TX_CLKP{slash}LVDS_TX_CLKP") (class "Default")
      (node (ref "CON0") (pin "48") (pinfunction "AG12/<MIPI_DSI_TX_CLKP/LVDS_TX_CLKP>_48") (pintype "passive"))
    )
    (net (code "95") (name "AG13{slash}MIPI_DSI_TX_D1N{slash}LVDS_TX_D1N") (class "Default")
      (node (ref "CON0") (pin "44") (pinfunction "AG13/<MIPI_DSI_TX_D1N/LVDS_TX_D1N>_44") (pintype "passive"))
    )
    (net (code "96") (name "AG14{slash}MIPI_DSI_TX_D0P{slash}LVDS_TX_D0P") (class "Default")
      (node (ref "CON0") (pin "51") (pinfunction "AG14/<MIPI_DSI_TX_D0P/LVDS_TX_D0P>_51") (pintype "passive"))
    )
    (net (code "97") (name "AG17{slash}SPI0_CSN0_M0{slash}3V3") (class "Default")
      (node (ref "CON0") (pin "72") (pinfunction "AG17/<UART2_CTSN_M0/PWM5_M0/SPI0_CSN0_M0/GPIO0_C2_d>/3V3_72") (pintype "passive"))
    )
    (net (code "98") (name "AG19{slash}SPI0_MOSI_M0{slash}3V3") (class "Default")
      (node (ref "CON0") (pin "73") (pinfunction "AG19/<UART6_CTSN_M0/PWM1_M0/SPI0_MOSI_M0/GPIO0_C4_d>/3V3_73") (pintype "passive"))
    )
    (net (code "99") (name "AG23{slash}I2C0_SCL{slash}PU{slash}3V3") (class "Default")
      (node (ref "CON0") (pin "86") (pinfunction "AG23/<I2C0_SCL/GPIO0_B1_d>/3V3_86") (pintype "passive"))
      (node (ref "R7") (pin "1") (pinfunction "1_1") (pintype "passive"))
    )
    (net (code "100") (name "D1{slash}CAM_CLK3_OUT{slash}3V3") (class "Default")
      (node (ref "CON0") (pin "151") (pinfunction "D1/<I2S1_SDO0_M1/CAM_CLK3_OUT/UART8_RTSN_M0/SPI0_CLK_M1/PWM13_M1/GPIO3_B5_d>/3V3_151") (pintype "passive"))
    )
    (net (code "101") (name "D3{slash}UART9_RX_M1{slash}BT1{slash}BT2{slash}3V3") (class "Default")
      (node (ref "CON0") (pin "128") (pinfunction "D3/<I2C5_SDA_M0/ISP_FLASH_TRIGOUT/UART9_RX_M1/GPIO3_C3_d>/3V3_128") (pintype "passive"))
    )
    (net (code "102") (name "D25{slash}SARADC0_IN4") (class "Default")
      (node (ref "CON0") (pin "193") (pinfunction "D25/<SARADC0_IN4>_193") (pintype "passive"))
    )
    (net (code "103") (name "D26{slash}SARADC0_BOOT{slash}Maskrom") (class "Default")
      (node (ref "CON0") (pin "121") (pinfunction "D26/<SARADC0_BOOT>_121") (pintype "passive"))
    )
    (net (code "104") (name "E1{slash}UART9_TX_M1{slash}BT1{slash}BT2{slash}3V3") (class "Default")
      (node (ref "CON0") (pin "127") (pinfunction "E1/<I2C5_SCL_M0/ISP_PRELIGHT_TRIGOUT/UART9_TX_M1/GPIO3_C2_d>/3V3_127") (pintype "passive"))
    )
    (net (code "105") (name "E2{slash}UART3_RTSN_M1{slash}RS485_RD{slash}3V3") (class "Default")
      (node (ref "CON0") (pin "131") (pinfunction "E2/<I2S1_SDI0_M1/ISP_FLASH_TRIGIN/UART3_RTSN_M1/GPIO3_C1_d>/3V3_131") (pintype "passive"))
    )
    (net (code "106") (name "E25{slash}SARADC0_IN2") (class "Default")
      (node (ref "CON0") (pin "191") (pinfunction "E25/<SARADC0_IN2>_191") (pintype "passive"))
    )
    (net (code "107") (name "E26{slash}SARADC0_IN5") (class "Default")
      (node (ref "CON0") (pin "194") (pinfunction "E26/<SARADC0_IN5>_194") (pintype "passive"))
    )
    (net (code "108") (name "E27{slash}SARADC0_IN6") (class "Default")
      (node (ref "CON0") (pin "195") (pinfunction "E27/<SARADC0_IN6>_195") (pintype "passive"))
    )
    (net (code "109") (name "F2{slash}CAM_CLK2_OUT{slash}3V3") (class "Default")
      (node (ref "CON0") (pin "149") (pinfunction "F2/<I2S1_LRCK_M1/CAM_CLK2_OUT/UART8_CTSN_M0/SPI0_MOSI_M1/PWM12_M1/GPIO3_B4_d>/3V3_149") (pintype "passive"))
    )
    (net (code "110") (name "F25{slash}SARADC0_IN7") (class "Default")
      (node (ref "CON0") (pin "196") (pinfunction "F25/<SARADC0_IN7>_196") (pintype "passive"))
    )
    (net (code "111") (name "F26{slash}SARADC0_IN1{slash}KEY{slash}RECOVERY") (class "Default")
      (node (ref "CON0") (pin "122") (pinfunction "F26/<SARADC0_IN1>_122") (pintype "passive"))
    )
    (net (code "112") (name "G1{slash}CAM_CLK1_OUT_M0{slash}3V3") (class "Default")
      (node (ref "CON0") (pin "150") (pinfunction "G1/<I2S1_SCLK_M1/CAM_CLK1_OUT_M0/UART8_RX_M0/GPIO3_B3_d>/3V3_150") (pintype "passive"))
    )
    (net (code "113") (name "G2{slash}UART3_TX_M1{slash}RS485{slash}3V3") (class "Default")
      (node (ref "CON0") (pin "129") (pinfunction "G2/<I2S1_SDO2_M1/I2S1_SDI2_M1/UART3_TX_M1/SPI0_CSN0_\nM1/I2C4_SDA_M0/CAN0_RX_M1/GPIO3_B7_d>/3V3_129") (pintype "passive"))
    )
    (net (code "114") (name "G3{slash}GPIO3_B6_d{slash}WAKE_HOST{slash}USBCC_INTn{slash}3V3") (class "Default")
      (node (ref "CON0") (pin "124") (pinfunction "G3/<I2S1_SDO1_M1/I2S1_SDI3_M1/UART3_CTSN_M1/SPI0_CSN\n1_M1/I2C4_SCL_M0/CAN0_TX_M1/GPIO3_B6_d>/3V3_124") (pintype "passive"))
    )
    (net (code "115") (name "G26{slash}SARADC0_IN3") (class "Default")
      (node (ref "CON0") (pin "192") (pinfunction "G26/<SARADC0_IN3>_192") (pintype "passive"))
    )
    (net (code "116") (name "GND") (class "Default")
      (node (ref "C1") (pin "2") (pinfunction "2_2") (pintype "passive"))
      (node (ref "C2") (pin "2") (pinfunction "2_2") (pintype "passive"))
      (node (ref "C5") (pin "1") (pinfunction "1_1") (pintype "passive"))
      (node (ref "C6") (pin "1") (pinfunction "1_1") (pintype "passive"))
      (node (ref "C7") (pin "2") (pinfunction "2_2") (pintype "passive"))
      (node (ref "C8") (pin "2") (pinfunction "2_2") (pintype "passive"))
      (node (ref "C9") (pin "2") (pinfunction "2_2") (pintype "passive"))
      (node (ref "CON0") (pin "108") (pinfunction "GND_108") (pintype "power_in"))
      (node (ref "CON0") (pin "115") (pinfunction "GND_115") (pintype "power_in"))
      (node (ref "CON0") (pin "119") (pinfunction "GND_119") (pintype "power_in"))
      (node (ref "CON0") (pin "123") (pinfunction "GND_123") (pintype "power_in"))
      (node (ref "CON0") (pin "13") (pinfunction "GND_13") (pintype "power_in"))
      (node (ref "CON0") (pin "133") (pinfunction "GND_133") (pintype "power_in"))
      (node (ref "CON0") (pin "139") (pinfunction "GND_139") (pintype "power_in"))
      (node (ref "CON0") (pin "147") (pinfunction "GND_147") (pintype "power_in"))
      (node (ref "CON0") (pin "152") (pinfunction "GND_152") (pintype "power_in"))
      (node (ref "CON0") (pin "158") (pinfunction "GND_158") (pintype "power_in"))
      (node (ref "CON0") (pin "165") (pinfunction "GND_165") (pintype "power_in"))
      (node (ref "CON0") (pin "179") (pinfunction "GND_179") (pintype "power_in"))
      (node (ref "CON0") (pin "20") (pinfunction "GND_20") (pintype "power_in"))
      (node (ref "CON0") (pin "27") (pinfunction "GND_27") (pintype "power_in"))
      (node (ref "CON0") (pin "34") (pinfunction "GND_34") (pintype "power_in"))
      (node (ref "CON0") (pin "45") (pinfunction "GND_45") (pintype "power_in"))
      (node (ref "CON0") (pin "50") (pinfunction "GND_50") (pintype "power_in"))
      (node (ref "CON0") (pin "53") (pinfunction "GND_53") (pintype "power_in"))
      (node (ref "CON0") (pin "56") (pinfunction "GND_56") (pintype "power_in"))
      (node (ref "CON0") (pin "59") (pinfunction "GND_59") (pintype "power_in"))
      (node (ref "CON0") (pin "62") (pinfunction "GND_62") (pintype "power_in"))
      (node (ref "CON0") (pin "65") (pinfunction "GND_65") (pintype "power_in"))
      (node (ref "CON0") (pin "68") (pinfunction "GND_68") (pintype "power_in"))
      (node (ref "CON0") (pin "76") (pinfunction "GND_76") (pintype "power_in"))
      (node (ref "CON0") (pin "87") (pinfunction "GND_87") (pintype "power_in"))
      (node (ref "CON0") (pin "97") (pinfunction "GND_97") (pintype "power_in"))
    )
    (net (code "117") (name "H2{slash}UART3_RX_M1{slash}RS485{slash}3V3") (class "Default")
      (node (ref "CON0") (pin "130") (pinfunction "H2/<I2S1_SDO3_M1/I2S1_SDI1_M1/UART3_RX_M1/SPI0_MISO_M1/GPIO3_C0_d>/3V3_130") (pintype "passive"))
    )
    (net (code "118") (name "H3{slash}CAM_CLK0_OUT_M0{slash}3V3") (class "Default")
      (node (ref "CON0") (pin "148") (pinfunction "H3/<I2S1_MCLK_M1/CAM_CLK0_OUT_M0/UART8_TX_M0/GPIO3_B2_d>/3V3_148") (pintype "passive"))
    )
    (net (code "119") (name "J1{slash}PDM_CLK0_M0{slash}PCIE20_CLKREQN_M1{slash}3V3") (class "Default")
      (node (ref "CON0") (pin "146") (pinfunction "J1/<I2S0_SDO1_M0/I2S0_SDI3_M0/PDM_CLK0_M0/PCIE20_CLKREQN_M1/UART5_TX_M1/GPIO3_A6_d>/3V3_146") (pintype "passive"))
      (node (ref "R15") (pin "1") (pinfunction "1_1") (pintype "passive"))
    )
    (net (code "120") (name "J2{slash}I2S0_SDI0_M0{slash}PMIC{slash}BT{slash}3V3") (class "Default")
      (node (ref "CON0") (pin "170") (pinfunction "J2/<I2S0_SDI0_M0/PDM_SDI0_M0/GPIO3_B1_d>/3V3_170") (pintype "passive"))
      (node (ref "R14") (pin "1") (pinfunction "1_1") (pintype "passive"))
    )
    (net (code "121") (name "K2{slash}I2S0_MCLK_M0{slash}PMIC{slash}3V3") (class "Default")
      (node (ref "CON0") (pin "166") (pinfunction "K2/<I2S0_MCLK_M0/UART2_CTSN_M1/PDM_CLK1_M0/GPIO3_A2_d>/3V3_166") (pintype "passive"))
      (node (ref "R10") (pin "1") (pinfunction "1_1") (pintype "passive"))
    )
    (net (code "122") (name "K3{slash}I2S0_SDO0_M0{slash}PMIC{slash}BT{slash}3V3") (class "Default")
      (node (ref "CON0") (pin "169") (pinfunction "K3/<I2S0_SDO0_M0/PWM9_M0/GPIO3_A5_d>/3V3_169") (pintype "passive"))
      (node (ref "R13") (pin "1") (pinfunction "1_1") (pintype "passive"))
    )
    (net (code "123") (name "L1{slash}I2S0_LRCK_M0{slash}PMIC{slash}BT{slash}3V3") (class "Default")
      (node (ref "CON0") (pin "168") (pinfunction "L1/<I2S0_LRCK_M0/PWM8_M0/GPIO3_A4_d>/3V3_168") (pintype "passive"))
      (node (ref "R12") (pin "1") (pinfunction "1_1") (pintype "passive"))
    )
    (net (code "124") (name "L2{slash}PCIE20_WAKEN_M1{slash}3V3") (class "Default")
      (node (ref "CON0") (pin "135") (pinfunction "L2/<I2S0_SDO2_M0/I2S0_SDI2_M0/PDM_SDI2_M0/PCIE20_WAKEN_M1/UART5_RX_M1/GPIO3_A7_d>/3V3_135") (pintype "passive"))
    )
    (net (code "125") (name "L3{slash}I2S0_SCLK_M0{slash}PMIC{slash}BT{slash}3V3") (class "Default")
      (node (ref "CON0") (pin "167") (pinfunction "L3/<I2S0_SCLK_M0/UART2_RTSN_M1/GPIO3_A3_d>/3V3_167") (pintype "passive"))
      (node (ref "R11") (pin "1") (pinfunction "1_1") (pintype "passive"))
    )
    (net (code "126") (name "M2{slash}SPI2_CSN1_M0{slash}CAN{slash}3V3") (class "Default")
      (node (ref "CON0") (pin "154") (pinfunction "M2/<VO_LCDC_HSYNC/I2S1_SDO1_M0/UART9_CTSN_M0/SPI2_CSN1_M0/I2C1_SCL_M1/UART3_TX_M0/GPIO4_B4_d>/3V3_154") (pintype "passive"))
    )
    (net (code "127") (name "M3{slash}SPI2_CSN0_M0{slash}CAN{slash}3V3") (class "Default")
      (node (ref "CON0") (pin "155") (pinfunction "M3/<VO_LCDC_VSYNC/I2S1_SDO2_M0/UART9_RTSN_M0/SPI2_CSN0_M0/I2C1_SDA_M1/UART3_RX_M0/GPIO4_B5_d>/3V3_155") (pintype "passive"))
    )
    (net (code "128") (name "N1{slash}GPIO3_C4_d{slash}CAN1_nINT{slash}3V3") (class "Default")
      (node (ref "CON0") (pin "143") (pinfunction "N1/<VO_LCDC_D3/I2S1_MCLK_M0/UART7_TX_M0/GPIO3_C4_d>/3V3_143") (pintype "passive"))
    )
    (net (code "129") (name "N2{slash}PWM14_M0{slash}LVDS_MIPI{slash}CSI{slash}3V3") (class "Default")
      (node (ref "CON0") (pin "142") (pinfunction "N2/<VO_LCDC_D4/I2S1_SCLK_M0/UART4_CTSN_M0/PWM14_M0/GPIO3_C5_d>/3V3_142") (pintype "passive"))
    )
    (net (code "130") (name "N3{slash}SPI2_CLK_M0{slash}CAN{slash}3V3") (class "Default")
      (node (ref "R1") (pin "2") (pinfunction "2_2") (pintype "passive"))
    )
    (net (code "131") (name "N25{slash}SDMMC0_D2{slash}JTAG_CPU_MCU_TCK_M1{slash}ADJ") (class "Default")
      (node (ref "CON0") (pin "114") (pinfunction "N25/<SDMMC0_D2/JTAG_CPU_MCU_TCK_M1/UART5_CTSN_M0/SPI1_CSN1_M1/PWM10_M0/DSM_AUD_RP/GPIO1_B5_u>/ADJ_114") (pintype "passive"))
    )
    (net (code "132") (name "N26{slash}SDMMC0_D3{slash}JTAG_CPU_MCU_TMS_M1{slash}ADJ") (class "Default")
      (node (ref "CON0") (pin "110") (pinfunction "N26/<SDMMC0_D3/JTAG_CPU_MCU_TMS_M1/UART5_RTSN_M0/SPI1_CSN0_M1/PWM11_M0/DSM_AUD_RN/GPIO1_B6_u>/ADJ_110") (pintype "passive"))
    )
    (net (code "133") (name "Net-(CON0B-AC26{slash}<PCIE20_REFCLKP>)") (class "Default")
      (node (ref "CON0") (pin "63") (pinfunction "AC26/<PCIE20_REFCLKP>_63") (pintype "passive"))
      (node (ref "R8") (pin "1") (pinfunction "1_1") (pintype "passive"))
    )
    (net (code "134") (name "Net-(CON0B-AC27{slash}<PCIE20_REFCLKN>)") (class "Default")
      (node (ref "CON0") (pin "64") (pinfunction "AC27/<PCIE20_REFCLKN>_64") (pintype "passive"))
      (node (ref "R9") (pin "1") (pinfunction "1_1") (pintype "passive"))
    )
    (net (code "135") (name "Net-(CON0C-1J14{slash}<SDMMC1_PWREN{slash}RGMII_MDC_M1{slash}PWM2_M1{slash}I2C5_SCL_M1{slash}RMII_MDC{slash}GPIO1_C7_d>{slash}3V3)") (class "Default")
      (node (ref "CON0") (pin "98") (pinfunction "1J14/<SDMMC1_PWREN/RGMII_MDC_M1/PWM2_M1/I2C5_SCL_M1/RMII_MDC/GPIO1_C7_d>/3V3_98") (pintype "passive"))
      (node (ref "R421") (pin "1") (pinfunction "1_1") (pintype "passive"))
    )
    (net (code "136") (name "Net-(CON0C-V26{slash}<SDMMC1_DETN{slash}RGMII_MDIO_M1{slash}PWM3_M1{slash}I2C5_SDA_M1{slash}RMII_MDIO{slash}GPIO1_D0_d>{slash}3V3)") (class "Default")
      (node (ref "CON0") (pin "99") (pinfunction "V26/<SDMMC1_DETN/RGMII_MDIO_M1/PWM3_M1/I2C5_SDA_M1/RMII_MDIO/GPIO1_D0_d>/3V3_99") (pintype "passive"))
      (node (ref "R455") (pin "1") (pinfunction "1_1") (pintype "passive"))
    )
    (net (code "137") (name "Net-(CON0D-AC1{slash}<VO_LCDC_D2{slash}RGMII_MDC_M0{slash}UART9_TX_M0{slash}GPIO4_B2_d>{slash}3V3)") (class "Default")
      (node (ref "CON0") (pin "160") (pinfunction "AC1/<VO_LCDC_D2/RGMII_MDC_M0/UART9_TX_M0/GPIO4_B2_d>/3V3_160") (pintype "passive"))
      (node (ref "R420") (pin "1") (pinfunction "1_1") (pintype "passive"))
    )
    (net (code "138") (name "Net-(CON0D-AC2{slash}<VO_LCDC_D18{slash}RGMII_MDIO_M0{slash}UART9_RX_M0{slash}GPIO4_B3_d>{slash}3V3)") (class "Default")
      (node (ref "CON0") (pin "159") (pinfunction "AC2/<VO_LCDC_D18/RGMII_MDIO_M0/UART9_RX_M0/GPIO4_B3_d>/3V3_159") (pintype "passive"))
      (node (ref "R454") (pin "1") (pinfunction "1_1") (pintype "passive"))
    )
    (net (code "139") (name "Net-(CON0D-N3{slash}<VO_LCDC_DEN{slash}I2S1_SDO3_M0{slash}UART3_CTSN_M0{slash}SPI2_CLK_M0{slash}GPIO4_B6_d>{slash}3V3)") (class "Default")
      (node (ref "CON0") (pin "153") (pinfunction "N3/<VO_LCDC_DEN/I2S1_SDO3_M0/UART3_CTSN_M0/SPI2_CLK_M0/GPIO4_B6_d>/3V3_153") (pintype "passive"))
      (node (ref "R1") (pin "1") (pinfunction "1_1") (pintype "passive"))
    )
    (net (code "140") (name "Net-(CON0D-T3{slash}<VO_LCDC_D12{slash}I2S1_SDI3_M0{slash}UART7_RTSN_M0{slash}SPI2_MOSI_M0{slash}I2C2_SDA_M1{slash}GPIO3_D3_d>{slash}3V3)") (class "Default")
      (node (ref "CON0") (pin "157") (pinfunction "T3/<VO_LCDC_D12/I2S1_SDI3_M0/UART7_RTSN_M0/SPI2_MOSI_M0/I2C2_SDA_M1/GPIO3_D3_d>/3V3_157") (pintype "passive"))
      (node (ref "R2") (pin "1") (pinfunction "1_1") (pintype "passive"))
    )
    (net (code "141") (name "Net-(CON0E-U25{slash}<SDMMC1_CLK{slash}RGMII_RXCLK_M1{slash}I2S0_MCLK_M1{slash}PWM1_M1{slash}GPIO1_C6_d>{slash}3V3)") (class "Default")
      (node (ref "CON0") (pin "175") (pinfunction "U25/<SDMMC1_CLK/RGMII_RXCLK_M1/I2S0_MCLK_M1/PWM1_M1/GPIO1_C6_d>/3V3_175") (pintype "passive"))
      (node (ref "R3") (pin "1") (pinfunction "1_1") (pintype "passive"))
    )
    (net (code "142") (name "P2{slash}GPIO3_C7_d{slash}CAN2_nINT{slash}3V3") (class "Default")
      (node (ref "CON0") (pin "144") (pinfunction "P2/<VO_LCDC_D6/I2S1_SDO0_M0/UART7_RX_M0/GPIO3_C7_d>/3V3_144") (pintype "passive"))
    )
    (net (code "143") (name "P3{slash}UART4_RTSN_M0{slash}RS485_RD{slash}3V3") (class "Default")
      (node (ref "CON0") (pin "145") (pinfunction "P3/<VO_LCDC_D5/I2S1_LRCK_M0/UART4_RTSN_M0/PWM15_M0/GPIO3_C6_d>/3V3_145") (pintype "passive"))
    )
    (net (code "144") (name "P25{slash}SDMMC0_CMD{slash}ADJ") (class "Default")
      (node (ref "CON0") (pin "113") (pinfunction "P25/<SDMMC0_CMD/SPDIF_TX_M2/UART5_RX_M0/CAN1_RX_M0/\nGPIO1_B7_u>/ADJ_113") (pintype "passive"))
    )
    (net (code "145") (name "P27{slash}SDMMC0_CLK{slash}ADJ") (class "Default")
      (node (ref "CON0") (pin "109") (pinfunction "P27/<SDMMC0_CLK/TEST_CLK_OUT/UART5_TX_M0/SPI1_CLK_M1\n/CAN1_TX_M0/GPIO1_C0_d>/ADJ_109") (pintype "passive"))
    )
    (net (code "146") (name "R1{slash}UART4_RX_M0{slash}RS485{slash}3V3") (class "Default")
      (node (ref "CON0") (pin "140") (pinfunction "R1/<VO_LCDC_D10/I2S1_SDI1_M0/UART4_RX_M0/UART3_RTSN_M0/GPIO3_D1_d>/3V3_140") (pintype "passive"))
    )
    (net (code "147") (name "R2{slash}SPI2_MISO_M0{slash}CAN{slash}3V3") (class "Default")
      (node (ref "CON0") (pin "156") (pinfunction "R2/<VO_LCDC_D11/I2S1_SDI2_M0/UART7_CTSN_M0/SPI2_MISO_M0/I2C2_SCL_M1/GPIO3_D2_d>/3V3_156") (pintype "passive"))
    )
    (net (code "148") (name "R3{slash}UART4_TX_M0{slash}RS485{slash}3V3") (class "Default")
      (node (ref "CON0") (pin "141") (pinfunction "R3/<VO_LCDC_D7/I2S1_SDI0_M0/UART4_TX_M0/GPIO3_D0_d>/3V3_141") (pintype "passive"))
    )
    (net (code "149") (name "R25{slash}SDMMC0_D0{slash}ADJ") (class "Default")
      (node (ref "CON0") (pin "112") (pinfunction "R25/<SDMMC0_D0/UART0_RX_M1/UART7_RX_M1/SPI1_MOSI_M1/DSM_AUD_LP/GPIO1_B3_u>/ADJ_112") (pintype "passive"))
    )
    (net (code "150") (name "R26{slash}SDMMC0_D1{slash}ADJ") (class "Default")
      (node (ref "CON0") (pin "111") (pinfunction "R26/<SDMMC0_D1/UART0_TX_M1/UART7_TX_M1/SPI1_MISO_M1/DSM_AUD_LN/GPIO1_B4_u>/ADJ_111") (pintype "passive"))
    )
    (net (code "151") (name "RK809_HPL_OUT") (class "Default")
      (node (ref "CON0") (pin "187") (pinfunction "RK809_HPL_OUT_187") (pintype "passive"))
    )
    (net (code "152") (name "RK809_HPR_OUT") (class "Default")
      (node (ref "CON0") (pin "188") (pinfunction "RK809_HPR_OUT_188") (pintype "passive"))
    )
    (net (code "153") (name "RK809_HP_SNS") (class "Default")
      (node (ref "CON0") (pin "186") (pinfunction "RK809_HP_SNS_186") (pintype "passive"))
    )
    (net (code "154") (name "RK809_MIC1n") (class "Default")
      (node (ref "C3") (pin "1") (pinfunction "1_1") (pintype "passive"))
    )
    (net (code "155") (name "RK809_MIC1p") (class "Default")
      (node (ref "C4") (pin "1") (pinfunction "1_1") (pintype "passive"))
    )
    (net (code "156") (name "RK809_PWRON{slash}PU{slash}3V3") (class "Default")
      (node (ref "CON0") (pin "117") (pinfunction "RK809_PWRON/PU/3V3_117") (pintype "passive"))
    )
    (net (code "157") (name "RK809_SPK_OUTn") (class "Default")
      (node (ref "C1") (pin "1") (pinfunction "1_1") (pintype "passive"))
      (node (ref "FB1") (pin "2") (pinfunction "2_2") (pintype "passive"))
    )
    (net (code "158") (name "RK809_SPK_OUTp") (class "Default")
      (node (ref "C2") (pin "1") (pinfunction "1_1") (pintype "passive"))
      (node (ref "FB2") (pin "2") (pinfunction "2_2") (pintype "passive"))
    )
    (net (code "159") (name "T2{slash}GPIO4_B1_d{slash}EVM_LED1{slash}3V3") (class "Default")
      (node (ref "CON0") (pin "137") (pinfunction "T2/<VO_LCDC_D17/ETH_CLK_25M_OUT_M0/CAM_CLK0_OUT_M1/I2S2_SCLK_M1/PDM_CLK1_M1/GPIO4_B1_d>/3V3_137") (pintype "passive"))
    )
    (net (code "160") (name "T3{slash}SPI2_MOSI_M0{slash}CAN{slash}3V3") (class "Default")
      (node (ref "R2") (pin "2") (pinfunction "2_2") (pintype "passive"))
    )
    (net (code "161") (name "T25{slash}SDMMC1_D2{slash}3V3") (class "Default")
      (node (ref "CON0") (pin "173") (pinfunction "T25/<SDMMC1_D2/RGMII_TXCLK_M1/I2S0_SDO0_M1/PWM10_M1/GPIO1_C3_d>/3V3_173") (pintype "passive"))
    )
    (net (code "162") (name "T26{slash}SDMMC1_D3{slash}3V3") (class "Default")
      (node (ref "CON0") (pin "174") (pinfunction "T26/<SDMMC1_D3/RGMII_RXD2_M1/I2S0_LRCK_M1/PWM11_M1/GPIO1_C4_d>/3V3_174") (pintype "passive"))
    )
    (net (code "163") (name "T27{slash}SDMMC1_CMD{slash}3V3") (class "Default")
      (node (ref "CON0") (pin "176") (pinfunction "T27/<SDMMC1_CMD/RGMII_RXD3_M1/I2S0_SCLK_M1/PWM0_M1/GPIO1_C5_d>/3V3_176") (pintype "passive"))
    )
    (net (code "164") (name "U1{slash}GPIO4_B7_d{slash}EVM_LED2{slash}3V3") (class "Default")
      (node (ref "CON0") (pin "138") (pinfunction "U1/<VO_LCDC_CLK/RGMII_CLK_M0/CAM_CLK1_OUT_M1/PDM_CLK0_M1/GPIO4_B7_d>/3V3_138") (pintype "passive"))
    )
    (net (code "165") (name "U2{slash}RGMII_RXCLK_M0{slash}3V3") (class "Default")
      (node (ref "CON0") (pin "12") (pinfunction "U2/<VO_LCDC_D21/RGMII_RXCLK_M0/I2S2_LRCK_M1/PWM12_M0/GPIO4_A1_d>/3V3_12") (pintype "passive"))
    )
    (net (code "166") (name "U25{slash}SDMMC1_CLK{slash}3V3") (class "Default")
      (node (ref "R3") (pin "2") (pinfunction "2_2") (pintype "passive"))
    )
    (net (code "167") (name "U26{slash}SDMMC1_D0{slash}3V3") (class "Default")
      (node (ref "CON0") (pin "171") (pinfunction "U26/<SDMMC1_D0/RGMII_TXD2_M1/I2S0_SDI0_M1/PWM8_M1/GPIO1_C1_d>/3V3_171") (pintype "passive"))
    )
    (net (code "168") (name "V2{slash}RGMII_RXDV_M0{slash}3V3") (class "Default")
      (node (ref "CON0") (pin "11") (pinfunction "V2/<VO_LCDC_D9/RGMII_RXDV_M0/UART1_RTSN_M1/PDM_SDI0_M1/UART6_TX_M1/GPIO4_A7_d>/3V3_11") (pintype "passive"))
    )
    (net (code "169") (name "V3{slash}GPIO4_B0_d{slash}MIPI_LVDS_CAP_TS_nINT{slash}3V3") (class "Default")
      (node (ref "CON0") (pin "134") (pinfunction "V3/<VO_LCDC_D16/RGMII_RXER_M0/UART1_CTSN_M1/PDM_SDI1_M1/UART6_RX_M1/GPIO4_B0_d>/3V3_134") (pintype "passive"))
    )
    (net (code "170") (name "V25{slash}SDMMC1_D1{slash}3V3") (class "Default")
      (node (ref "CON0") (pin "172") (pinfunction "V25/<SDMMC1_D1/RGMII_TXD3_M1/I2S0_SDI1_M1/PWM9_M1/GPIO1_C2_d>/3V3_172") (pintype "passive"))
    )
    (net (code "171") (name "V26{slash}RMII_MDIO{slash}3V3") (class "Default")
      (node (ref "R455") (pin "2") (pinfunction "2_2") (pintype "passive"))
    )
    (net (code "172") (name "V27{slash}RMII_RXDV_CRS{slash}3V3") (class "Default")
      (node (ref "CON0") (pin "105") (pinfunction "V27/<I2S2_LRCK_M0/RGMII_RXDV_M1/UART4_TX_M1/SPI2_CSN0_M1/RMII_RXDV_CRS/GPIO1_D6_d>/3V3_105") (pintype "passive"))
    )
    (net (code "173") (name "VDD_3V3_ACODEC") (class "Default")
      (node (ref "CON0") (pin "180") (pinfunction "VDD_3V3_ACODEC_180") (pintype "passive"))
    )
    (net (code "174") (name "VDD_3V3_MAIN") (class "Default")
      (node (ref "R4") (pin "2") (pinfunction "2_2") (pintype "passive"))
      (node (ref "R5") (pin "2") (pinfunction "2_2") (pintype "passive"))
      (node (ref "R6") (pin "2") (pinfunction "2_2") (pintype "passive"))
      (node (ref "R7") (pin "2") (pinfunction "2_2") (pintype "passive"))
    )
    (net (code "175") (name "VDD_3V3_SOM") (class "Default")
      (node (ref "C5") (pin "2") (pinfunction "2_2") (pintype "passive"))
      (node (ref "C6") (pin "2") (pinfunction "2_2") (pintype "passive"))
      (node (ref "C7") (pin "1") (pinfunction "1_1") (pintype "passive"))
      (node (ref "CON0") (pin "77") (pinfunction "VDD_3V3_SOM_77") (pintype "power_in"))
      (node (ref "CON0") (pin "78") (pinfunction "VDD_3V3_SOM_78") (pintype "power_in"))
      (node (ref "CON0") (pin "79") (pinfunction "VDD_3V3_SOM_79") (pintype "power_in"))
      (node (ref "CON0") (pin "80") (pinfunction "VDD_3V3_SOM_80") (pintype "power_in"))
    )
    (net (code "176") (name "VDD_3V3_SOM_OUT") (class "Default")
      (node (ref "CON0") (pin "120") (pinfunction "VDD_3V3_SOM_OUT_120") (pintype "passive"))
    )
    (net (code "177") (name "W1{slash}RGMII_RXD1_M0{slash}3V3") (class "Default")
      (node (ref "CON0") (pin "9") (pinfunction "W1/<VO_LCDC_D8/RGMII_RXD1_M0/UART1_RX_M1/PDM_SDI3_M1/I2C3_SDA_M1/GPIO4_A6_d>/3V3_9") (pintype "passive"))
    )
    (net (code "178") (name "W2{slash}RGMII_RXD2_M0{slash}3V3") (class "Default")
      (node (ref "CON0") (pin "8") (pinfunction "W2/<VO_LCDC_D19/RGMII_RXD2_M0/UART8_CTSN_M1/SPI1_CSN0_M0/GPIO3_D7_d>/3V3_8") (pintype "passive"))
    )
    (net (code "179") (name "W3{slash}RGMII_RXD0_M0{slash}3V3") (class "Default")
      (node (ref "CON0") (pin "7") (pinfunction "W3/<VO_LCDC_D1/RGMII_RXD0_M0/UART1_TX_M1/PDM_SDI2_M1/I2C3_SCL_M1/GPIO4_A5_d>/3V3_7") (pintype "passive"))
    )
    (net (code "180") (name "W25{slash}GPIO2_A1_d{slash}TOUCH_INTn{slash}3V3") (class "Default")
      (node (ref "CON0") (pin "71") (pinfunction "W25/<I2S2_MCLK_M0/ETH_CLK_25M_OUT_M1/CLK1_32K_OUT/SPI2_CLK_M1/I2S0_SDO3_M1/GPIO2_A1_d>/3V3_71") (pintype "passive"))
    )
    (net (code "181") (name "W26{slash}RMII_CLK{slash}3V3") (class "Default")
      (node (ref "CON0") (pin "107") (pinfunction "W26/<I2S2_SCLK_M0/RGMII_CLK_M1/UART4_RX_M1/SPI2_CSN1_M1/RMII_CLK/GPIO1_D5_d>/3V3_107") (pintype "passive"))
    )
    (net (code "182") (name "Y2{slash}RGMII_TXCLK_M0{slash}3V3") (class "Default")
      (node (ref "CON0") (pin "1") (pinfunction "Y2/<VO_LCDC_D15/RGMII_TXCLK_M0/I2S2_MCLK_M1/SPI1_CLK_M0/GPIO3_D6_d>/3V3_1") (pintype "passive"))
    )
    (net (code "183") (name "Y3{slash}RGMII_RXD3_M0{slash}3V3") (class "Default")
      (node (ref "CON0") (pin "10") (pinfunction "Y3/<VO_LCDC_D20/RGMII_RXD3_M0/UART8_RTSN_M1/SPI1_CSN1_M0/GPIO4_A0_d>/3V3_10") (pintype "passive"))
    )
    (net (code "184") (name "Y25{slash}RMII_TXD0{slash}3V3") (class "Default")
      (node (ref "CON0") (pin "104") (pinfunction "Y25/<UART1_RX_M0/RGMII_TXD0_M1/I2S0_SDO1_M1/PWM4_M1/RMII_TXD0/GPIO1_D1_d>/3V3_104") (pintype "passive"))
    )
    (net (code "185") (name "Y26{slash}RMII_TXD1{slash}3V3") (class "Default")
      (node (ref "CON0") (pin "106") (pinfunction "Y26/<UART1_TX_M0/RGMII_TXD1_M1/I2S0_SDO2_M1/PWM5_M1/RMII_TXD1/GPIO1_D2_d>/3V3_106") (pintype "passive"))
    )
    (net (code "186") (name "Y27{slash}RMII_RXD0{slash}3V3") (class "Default")
      (node (ref "CON0") (pin "101") (pinfunction "Y27/<UART1_CTSN_M0/RGMII_RXD0_M1/I2S0_SDI3_M1/PWM7_M1/RMII_RXD0/GPIO1_D4_d>/3V3_101") (pintype "passive"))
    )
  )
)
